# Power.net
KiCad netlist of a schematic drawn in EAGLE
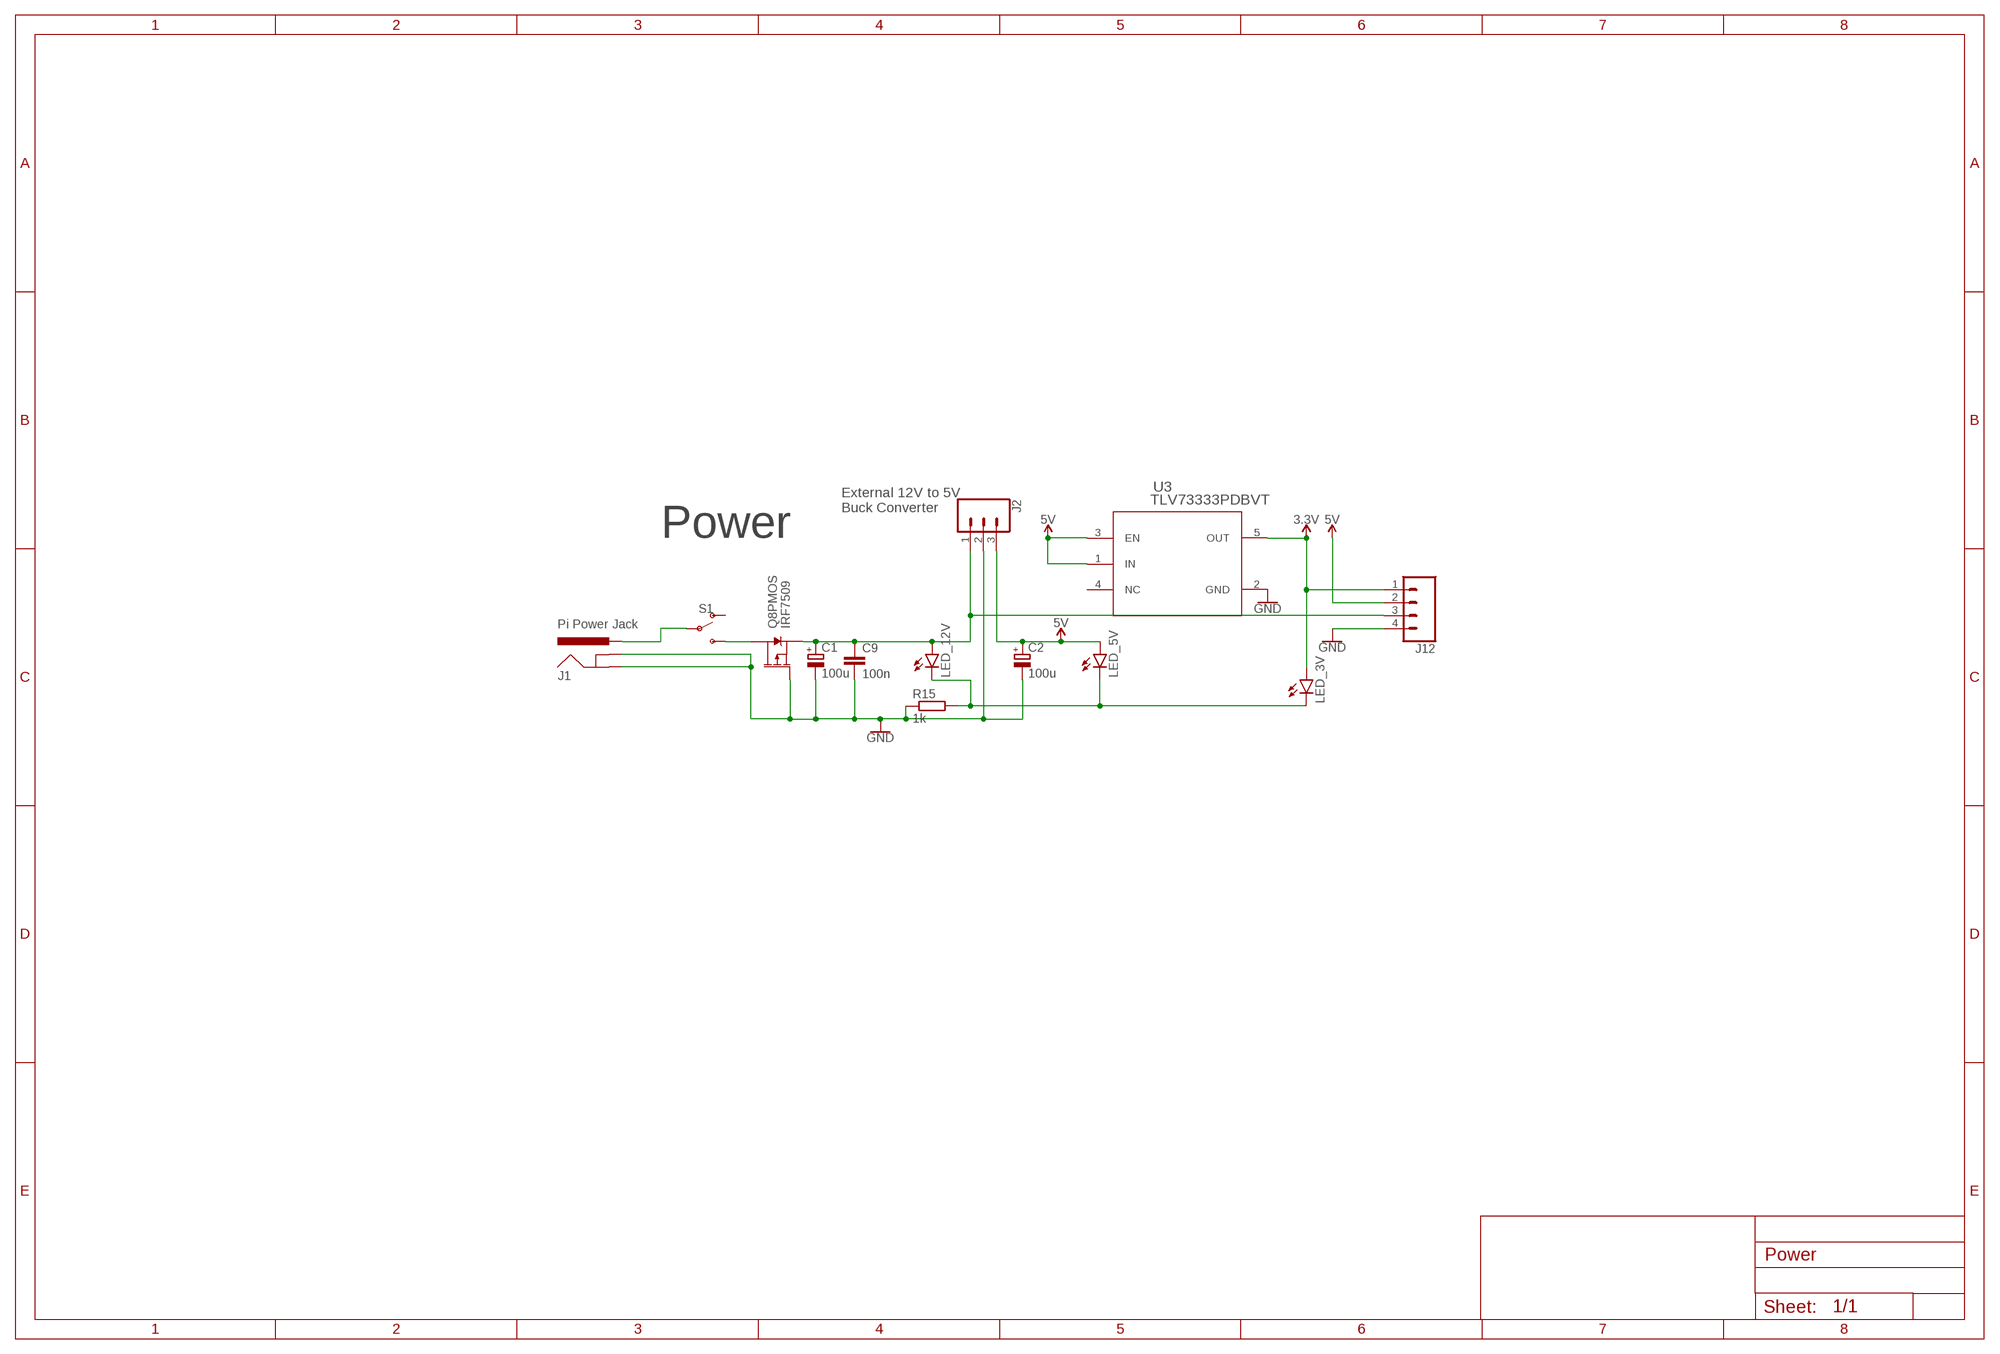
[diagram p0: schematic, sheet 1]

(export (version "E")
  (design (tool "Eeschema 10.0.6"))
  (components
    (comp (ref "C1")
      (value "100u")
      (footprint "eagle-import:E2-5")
      (libsource (lib "eagle-import") (part "CPOL-EUE2-5"))
    )
    (comp (ref "C2")
      (value "100u")
      (footprint "eagle-import:E2-5")
      (libsource (lib "eagle-import") (part "CPOL-EUE2-5"))
    )
    (comp (ref "C9")
      (value "100n")
      (footprint "eagle-import:C0805")
      (libsource (lib "eagle-import") (part "C-EUC0805"))
    )
    (comp (ref "J1")
      (value "Pi Power Jack")
      (footprint "eagle-import:POWER_JACK_PTH_BREAD")
      (libsource (lib "eagle-import") (part "POWER_JACKPTH_BREAD"))
    )
    (comp (ref "J2")
      (value "Header - Right angled, female")
      (footprint "eagle-import:1X03")
      (libsource (lib "eagle-import") (part "CONN_031X03_2.54MM_RA_FEMALE"))
    )
    (comp (ref "J12")
      (value "CONN_04JST-PTH")
      (footprint "eagle-import:JST-4-PTH")
      (libsource (lib "eagle-import") (part "CONN_04JST-PTH"))
    )
    (comp (ref "LED_3V")
      (value "LEDCHIP-LED0805")
      (footprint "eagle-import:CHIP-LED0805")
      (libsource (lib "eagle-import") (part "LEDCHIP-LED0805"))
    )
    (comp (ref "LED_5V")
      (value "LEDCHIP-LED0805")
      (footprint "eagle-import:CHIP-LED0805")
      (libsource (lib "eagle-import") (part "LEDCHIP-LED0805"))
    )
    (comp (ref "LED_12V")
      (value "LEDCHIP-LED0805")
      (footprint "eagle-import:CHIP-LED0805")
      (libsource (lib "eagle-import") (part "LEDCHIP-LED0805"))
    )
    (comp (ref "Q8")
      (value "IRF7509")
      (footprint "eagle-import:MSOP8")
      (libsource (lib "eagle-import") (part "IRF7509"))
    )
    (comp (ref "R15")
      (value "1k")
      (footprint "eagle-import:M0805")
      (libsource (lib "eagle-import") (part "R-EU_M0805"))
    )
    (comp (ref "S1")
      (value "SWITCH-SPDT-PTH-11.6X4.0MM")
      (footprint "eagle-import:SWITCH_SPDT_PTH_11.6X4.0MM")
      (libsource (lib "eagle-import") (part "SWITCH-SPDT-PTH-11.6X4.0MM"))
    )
    (comp (ref "U3")
      (value "TLV73333PDBVT")
      (footprint "eagle-import:DBV5")
      (libsource (lib "eagle-import") (part "TLV73333PDBVT"))
    )
  )
  (nets
    (net (code "1") (name "3.3V") (class "Default")
      (node (ref "J12") (pin "1") (pinfunction "1_1") (pintype "passive"))
      (node (ref "LED_3V") (pin "A") (pinfunction "A_A") (pintype "passive"))
      (node (ref "U3") (pin "5") (pinfunction "OUT_5") (pintype "output"))
    )
    (net (code "2") (name "5V") (class "Default")
      (node (ref "C2") (pin "+") (pinfunction "+_+") (pintype "passive"))
      (node (ref "J12") (pin "2") (pinfunction "2_2") (pintype "passive"))
      (node (ref "J2") (pin "3") (pinfunction "3_3") (pintype "passive"))
      (node (ref "LED_5V") (pin "A") (pinfunction "A_A") (pintype "passive"))
      (node (ref "U3") (pin "1") (pinfunction "IN_1") (pintype "passive"))
      (node (ref "U3") (pin "3") (pinfunction "EN_3") (pintype "input"))
    )
    (net (code "3") (name "GND") (class "Default")
      (node (ref "C1") (pin "-") (pinfunction "-_-") (pintype "passive"))
      (node (ref "C2") (pin "-") (pinfunction "-_-") (pintype "passive"))
      (node (ref "C9") (pin "2") (pinfunction "2_2") (pintype "passive"))
      (node (ref "J1") (pin "GND") (pinfunction "GND_GND") (pintype "bidirectional"))
      (node (ref "J1") (pin "GNDBREAK") (pinfunction "GNDBREAK_GNDBREAK") (pintype "bidirectional"))
      (node (ref "J12") (pin "4") (pinfunction "4_4") (pintype "passive"))
      (node (ref "J2") (pin "2") (pinfunction "2_2") (pintype "passive"))
      (node (ref "Q8") (pin "4") (pinfunction "G_4") (pintype "bidirectional"))
      (node (ref "R15") (pin "1") (pinfunction "1_1") (pintype "passive"))
      (node (ref "U3") (pin "2") (pinfunction "GND_2") (pintype "power_in"))
    )
    (net (code "4") (name "Net-(LED_12V-PadC)") (class "Default")
      (node (ref "LED_12V") (pin "C") (pinfunction "C_C") (pintype "passive"))
      (node (ref "LED_3V") (pin "C") (pinfunction "C_C") (pintype "passive"))
      (node (ref "LED_5V") (pin "C") (pinfunction "C_C") (pintype "passive"))
      (node (ref "R15") (pin "2") (pinfunction "2_2") (pintype "passive"))
    )
    (net (code "5") (name "Net-(Q8B-S)") (class "Default")
      (node (ref "C1") (pin "+") (pinfunction "+_+") (pintype "passive"))
      (node (ref "C9") (pin "1") (pinfunction "1_1") (pintype "passive"))
      (node (ref "J12") (pin "3") (pinfunction "3_3") (pintype "passive"))
      (node (ref "J2") (pin "1") (pinfunction "1_1") (pintype "passive"))
      (node (ref "LED_12V") (pin "A") (pinfunction "A_A") (pintype "passive"))
      (node (ref "Q8") (pin "3") (pinfunction "S_3") (pintype "bidirectional"))
    )
    (net (code "6") (name "Net-(S1-P)") (class "Default")
      (node (ref "J1") (pin "PWR") (pinfunction "PWR_PWR") (pintype "bidirectional"))
      (node (ref "S1") (pin "2") (pinfunction "P_2") (pintype "passive"))
    )
    (net (code "7") (name "Net-(S1-S)") (class "Default")
      (node (ref "Q8") (pin "5") (pinfunction "D_5") (pintype "bidirectional"))
      (node (ref "Q8") (pin "6") (pinfunction "D_6") (pintype "bidirectional"))
      (node (ref "S1") (pin "3") (pinfunction "S_3") (pintype "passive"))
    )
    (net (code "8") (name "unconnected-(S1-O-Pad1)") (class "Default")
      (node (ref "S1") (pin "1") (pinfunction "O_1") (pintype "passive"))
    )
    (net (code "9") (name "unconnected-(U3-NC-Pad4)") (class "Default")
      (node (ref "U3") (pin "4") (pinfunction "NC_4") (pintype "no_connect"))
    )
  )
)
